# sumobot2.net
KiCad netlist of a schematic drawn in EAGLE
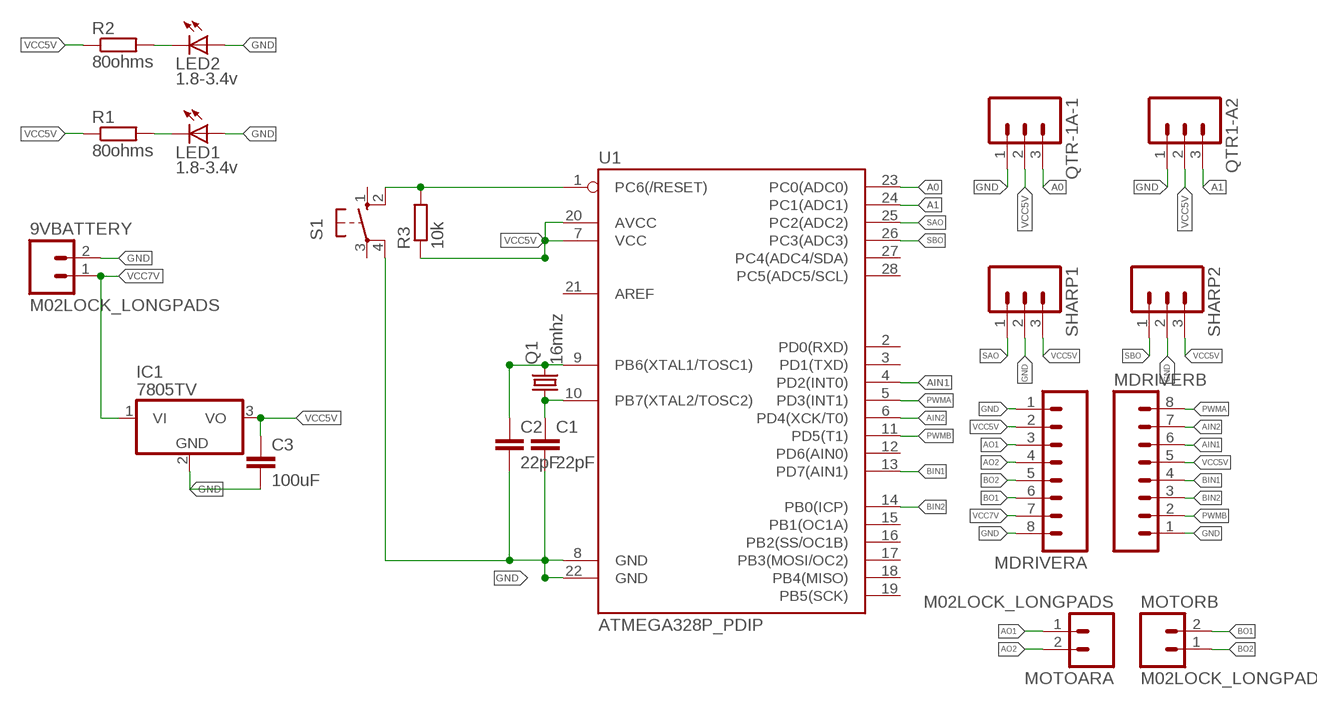
[diagram p0: schematic, sheet 1]

(export (version "E")
  (design (tool "Eeschema 10.0.6"))
  (components
    (comp (ref "9VBATTERY")
      (value "M02LOCK_LONGPADS")
      (footprint "eagle-import:1X02_LOCK_LONGPADS")
      (libsource (lib "eagle-import") (part "M02LOCK_LONGPADS"))
    )
    (comp (ref "C1")
      (value "22pF")
      (footprint "eagle-import:C025-025X050")
      (libsource (lib "eagle-import") (part "C-EU025-025X050"))
    )
    (comp (ref "C2")
      (value "22pF")
      (footprint "eagle-import:C025-025X050")
      (libsource (lib "eagle-import") (part "C-EU025-025X050"))
    )
    (comp (ref "C3")
      (value "100uF")
      (footprint "eagle-import:C025-025X050")
      (libsource (lib "eagle-import") (part "C-EU025-025X050"))
    )
    (comp (ref "IC1")
      (value "7805TV")
      (footprint "eagle-import:TO220V")
      (libsource (lib "eagle-import") (part "78TV05"))
    )
    (comp (ref "LED1")
      (value "1.8-3.4v")
      (footprint "eagle-import:LED3MM")
      (libsource (lib "eagle-import") (part "LED3MM"))
    )
    (comp (ref "LED2")
      (value "1.8-3.4v")
      (footprint "eagle-import:LED3MM")
      (libsource (lib "eagle-import") (part "LED3MM"))
    )
    (comp (ref "MDRIVERA")
      (value "M08LONGPADS")
      (footprint "eagle-import:1X08_LONGPADS")
      (libsource (lib "eagle-import") (part "M08LONGPADS"))
    )
    (comp (ref "MDRIVERB")
      (value "M08LONGPADS")
      (footprint "eagle-import:1X08_LONGPADS")
      (libsource (lib "eagle-import") (part "M08LONGPADS"))
    )
    (comp (ref "MOTOARA")
      (value "M02LOCK_LONGPADS")
      (footprint "eagle-import:1X02_LOCK_LONGPADS")
      (libsource (lib "eagle-import") (part "M02LOCK_LONGPADS"))
    )
    (comp (ref "MOTORB")
      (value "M02LOCK_LONGPADS")
      (footprint "eagle-import:1X02_LOCK_LONGPADS")
      (libsource (lib "eagle-import") (part "M02LOCK_LONGPADS"))
    )
    (comp (ref "Q1")
      (value "16mhz")
      (footprint "eagle-import:HC49U70")
      (libsource (lib "eagle-import") (part "CRYSTALHC49U70"))
    )
    (comp (ref "QTR-1A-1")
      (value "M03LONGPADS")
      (footprint "eagle-import:1X03_LONGPADS")
      (libsource (lib "eagle-import") (part "M03LONGPADS"))
    )
    (comp (ref "QTR1-A2")
      (value "M03LONGPADS")
      (footprint "eagle-import:1X03_LONGPADS")
      (libsource (lib "eagle-import") (part "M03LONGPADS"))
    )
    (comp (ref "R1")
      (value "80ohms")
      (footprint "eagle-import:0207_10")
      (libsource (lib "eagle-import") (part "R-EU_0207/10"))
    )
    (comp (ref "R2")
      (value "80ohms")
      (footprint "eagle-import:0207_10")
      (libsource (lib "eagle-import") (part "R-EU_0207/10"))
    )
    (comp (ref "R3")
      (value "10k")
      (footprint "eagle-import:0207_10")
      (libsource (lib "eagle-import") (part "R-EU_0207/10"))
    )
    (comp (ref "S1")
      (value "10-XX")
      (footprint "eagle-import:B3F-10XX")
      (fields (field (name "MPN") "B3F-1000"))
      (libsource (lib "eagle-import") (part "10-XX"))
    )
    (comp (ref "SHARP1")
      (value "M03LONGPADS")
      (footprint "eagle-import:1X03_LONGPADS")
      (libsource (lib "eagle-import") (part "M03LONGPADS"))
    )
    (comp (ref "SHARP2")
      (value "M03LONGPADS")
      (footprint "eagle-import:1X03_LONGPADS")
      (libsource (lib "eagle-import") (part "M03LONGPADS"))
    )
    (comp (ref "U1")
      (value "ATMEGA328P_PDIP")
      (footprint "eagle-import:DIL28-3")
      (libsource (lib "eagle-import") (part "ATMEGA328P_PDIP"))
    )
  )
  (nets
    (net (code "1") (name "A0") (class "Default")
      (node (ref "QTR-1A-1") (pin "3") (pinfunction "3_3") (pintype "passive"))
      (node (ref "U1") (pin "23") (pinfunction "PC0(ADC0)_23") (pintype "bidirectional"))
    )
    (net (code "2") (name "A1") (class "Default")
      (node (ref "QTR1-A2") (pin "3") (pinfunction "3_3") (pintype "passive"))
      (node (ref "U1") (pin "24") (pinfunction "PC1(ADC1)_24") (pintype "bidirectional"))
    )
    (net (code "3") (name "AIN1") (class "Default")
      (node (ref "MDRIVERB") (pin "6") (pinfunction "6_6") (pintype "passive"))
      (node (ref "U1") (pin "4") (pinfunction "PD2(INT0)_4") (pintype "bidirectional"))
    )
    (net (code "4") (name "AIN2") (class "Default")
      (node (ref "MDRIVERB") (pin "7") (pinfunction "7_7") (pintype "passive"))
      (node (ref "U1") (pin "6") (pinfunction "PD4(XCK/T0)_6") (pintype "bidirectional"))
    )
    (net (code "5") (name "AO1") (class "Default")
      (node (ref "MDRIVERA") (pin "3") (pinfunction "3_3") (pintype "passive"))
      (node (ref "MOTOARA") (pin "1") (pinfunction "1_1") (pintype "passive"))
    )
    (net (code "6") (name "AO2") (class "Default")
      (node (ref "MDRIVERA") (pin "4") (pinfunction "4_4") (pintype "passive"))
      (node (ref "MOTOARA") (pin "2") (pinfunction "2_2") (pintype "passive"))
    )
    (net (code "7") (name "BIN1") (class "Default")
      (node (ref "MDRIVERB") (pin "4") (pinfunction "4_4") (pintype "passive"))
      (node (ref "U1") (pin "13") (pinfunction "PD7(AIN1)_13") (pintype "bidirectional"))
    )
    (net (code "8") (name "BIN2") (class "Default")
      (node (ref "MDRIVERB") (pin "3") (pinfunction "3_3") (pintype "passive"))
      (node (ref "U1") (pin "14") (pinfunction "PB0(ICP)_14") (pintype "bidirectional"))
    )
    (net (code "9") (name "BO1") (class "Default")
      (node (ref "MDRIVERA") (pin "6") (pinfunction "6_6") (pintype "passive"))
      (node (ref "MOTORB") (pin "2") (pinfunction "2_2") (pintype "passive"))
    )
    (net (code "10") (name "BO2") (class "Default")
      (node (ref "MDRIVERA") (pin "5") (pinfunction "5_5") (pintype "passive"))
      (node (ref "MOTORB") (pin "1") (pinfunction "1_1") (pintype "passive"))
    )
    (net (code "11") (name "GND") (class "Default")
      (node (ref "9VBATTERY") (pin "2") (pinfunction "2_2") (pintype "passive"))
      (node (ref "C1") (pin "2") (pinfunction "2_2") (pintype "passive"))
      (node (ref "C2") (pin "2") (pinfunction "2_2") (pintype "passive"))
      (node (ref "C3") (pin "2") (pinfunction "2_2") (pintype "passive"))
      (node (ref "IC1") (pin "2") (pinfunction "GND_2") (pintype "passive"))
      (node (ref "LED1") (pin "A") (pinfunction "A_A") (pintype "passive"))
      (node (ref "LED2") (pin "A") (pinfunction "A_A") (pintype "passive"))
      (node (ref "MDRIVERA") (pin "1") (pinfunction "1_1") (pintype "passive"))
      (node (ref "MDRIVERA") (pin "8") (pinfunction "8_8") (pintype "passive"))
      (node (ref "MDRIVERB") (pin "1") (pinfunction "1_1") (pintype "passive"))
      (node (ref "QTR-1A-1") (pin "1") (pinfunction "1_1") (pintype "passive"))
      (node (ref "QTR1-A2") (pin "1") (pinfunction "1_1") (pintype "passive"))
      (node (ref "S1") (pin "4") (pinfunction "P1_4") (pintype "passive"))
      (node (ref "SHARP1") (pin "2") (pinfunction "2_2") (pintype "passive"))
      (node (ref "SHARP2") (pin "2") (pinfunction "2_2") (pintype "passive"))
      (node (ref "U1") (pin "22") (pinfunction "GND_22") (pintype "bidirectional"))
      (node (ref "U1") (pin "8") (pinfunction "GND_8") (pintype "bidirectional"))
    )
    (net (code "12") (name "Net-(LED1-C)") (class "Default")
      (node (ref "LED1") (pin "K") (pinfunction "C_K") (pintype "passive"))
      (node (ref "R1") (pin "2") (pinfunction "2_2") (pintype "passive"))
    )
    (net (code "13") (name "Net-(LED2-C)") (class "Default")
      (node (ref "LED2") (pin "K") (pinfunction "C_K") (pintype "passive"))
      (node (ref "R2") (pin "2") (pinfunction "2_2") (pintype "passive"))
    )
    (net (code "14") (name "Net-(S1-S1)") (class "Default")
      (node (ref "R3") (pin "2") (pinfunction "2_2") (pintype "passive"))
      (node (ref "S1") (pin "2") (pinfunction "S1_2") (pintype "passive"))
      (node (ref "U1") (pin "1") (pinfunction "PC6(/RESET)_1") (pintype "bidirectional"))
    )
    (net (code "15") (name "Net-(U1-PB6(XTAL1{slash}TOSC1))") (class "Default")
      (node (ref "C2") (pin "1") (pinfunction "1_1") (pintype "passive"))
      (node (ref "Q1") (pin "2") (pinfunction "2_2") (pintype "passive"))
      (node (ref "U1") (pin "9") (pinfunction "PB6(XTAL1/TOSC1)_9") (pintype "bidirectional"))
    )
    (net (code "16") (name "Net-(U1-PB7(XTAL2{slash}TOSC2))") (class "Default")
      (node (ref "C1") (pin "1") (pinfunction "1_1") (pintype "passive"))
      (node (ref "Q1") (pin "1") (pinfunction "1_1") (pintype "passive"))
      (node (ref "U1") (pin "10") (pinfunction "PB7(XTAL2/TOSC2)_10") (pintype "bidirectional"))
    )
    (net (code "17") (name "PWMA") (class "Default")
      (node (ref "MDRIVERB") (pin "8") (pinfunction "8_8") (pintype "passive"))
      (node (ref "U1") (pin "5") (pinfunction "PD3(INT1)_5") (pintype "bidirectional"))
    )
    (net (code "18") (name "PWMB") (class "Default")
      (node (ref "MDRIVERB") (pin "2") (pinfunction "2_2") (pintype "passive"))
      (node (ref "U1") (pin "11") (pinfunction "PD5(T1)_11") (pintype "bidirectional"))
    )
    (net (code "19") (name "SAO") (class "Default")
      (node (ref "SHARP1") (pin "1") (pinfunction "1_1") (pintype "passive"))
      (node (ref "U1") (pin "25") (pinfunction "PC2(ADC2)_25") (pintype "bidirectional"))
    )
    (net (code "20") (name "SBO") (class "Default")
      (node (ref "SHARP2") (pin "1") (pinfunction "1_1") (pintype "passive"))
      (node (ref "U1") (pin "26") (pinfunction "PC3(ADC3)_26") (pintype "bidirectional"))
    )
    (net (code "21") (name "VCC5V") (class "Default")
      (node (ref "C3") (pin "1") (pinfunction "1_1") (pintype "passive"))
      (node (ref "IC1") (pin "3") (pinfunction "VO_3") (pintype "passive"))
      (node (ref "MDRIVERA") (pin "2") (pinfunction "2_2") (pintype "passive"))
      (node (ref "MDRIVERB") (pin "5") (pinfunction "5_5") (pintype "passive"))
      (node (ref "QTR-1A-1") (pin "2") (pinfunction "2_2") (pintype "passive"))
      (node (ref "QTR1-A2") (pin "2") (pinfunction "2_2") (pintype "passive"))
      (node (ref "R1") (pin "1") (pinfunction "1_1") (pintype "passive"))
      (node (ref "R2") (pin "1") (pinfunction "1_1") (pintype "passive"))
      (node (ref "R3") (pin "1") (pinfunction "1_1") (pintype "passive"))
      (node (ref "SHARP1") (pin "3") (pinfunction "3_3") (pintype "passive"))
      (node (ref "SHARP2") (pin "3") (pinfunction "3_3") (pintype "passive"))
      (node (ref "U1") (pin "20") (pinfunction "AVCC_20") (pintype "bidirectional"))
      (node (ref "U1") (pin "7") (pinfunction "VCC_7") (pintype "bidirectional"))
    )
    (net (code "22") (name "VCC7V") (class "Default")
      (node (ref "9VBATTERY") (pin "1") (pinfunction "1_1") (pintype "passive"))
      (node (ref "IC1") (pin "1") (pinfunction "VI_1") (pintype "input"))
      (node (ref "MDRIVERA") (pin "7") (pinfunction "7_7") (pintype "passive"))
    )
    (net (code "23") (name "unconnected-(S1-P-Pad3)") (class "Default")
      (node (ref "S1") (pin "3") (pinfunction "P_3") (pintype "passive"))
    )
    (net (code "24") (name "unconnected-(S1-S-Pad1)") (class "Default")
      (node (ref "S1") (pin "1") (pinfunction "S_1") (pintype "passive"))
    )
    (net (code "25") (name "unconnected-(U1-AREF-Pad21)") (class "Default")
      (node (ref "U1") (pin "21") (pinfunction "AREF_21") (pintype "bidirectional"))
    )
    (net (code "26") (name "unconnected-(U1-PB1(OC1A)-Pad15)") (class "Default")
      (node (ref "U1") (pin "15") (pinfunction "PB1(OC1A)_15") (pintype "bidirectional"))
    )
    (net (code "27") (name "unconnected-(U1-PB2(SS{slash}OC1B)-Pad16)") (class "Default")
      (node (ref "U1") (pin "16") (pinfunction "PB2(SS/OC1B)_16") (pintype "bidirectional"))
    )
    (net (code "28") (name "unconnected-(U1-PB3(MOSI{slash}OC2)-Pad17)") (class "Default")
      (node (ref "U1") (pin "17") (pinfunction "PB3(MOSI/OC2)_17") (pintype "bidirectional"))
    )
    (net (code "29") (name "unconnected-(U1-PB4(MISO)-Pad18)") (class "Default")
      (node (ref "U1") (pin "18") (pinfunction "PB4(MISO)_18") (pintype "bidirectional"))
    )
    (net (code "30") (name "unconnected-(U1-PB5(SCK)-Pad19)") (class "Default")
      (node (ref "U1") (pin "19") (pinfunction "PB5(SCK)_19") (pintype "bidirectional"))
    )
    (net (code "31") (name "unconnected-(U1-PC4(ADC4{slash}SDA)-Pad27)") (class "Default")
      (node (ref "U1") (pin "27") (pinfunction "PC4(ADC4/SDA)_27") (pintype "bidirectional"))
    )
    (net (code "32") (name "unconnected-(U1-PC5(ADC5{slash}SCL)-Pad28)") (class "Default")
      (node (ref "U1") (pin "28") (pinfunction "PC5(ADC5/SCL)_28") (pintype "bidirectional"))
    )
    (net (code "33") (name "unconnected-(U1-PD0(RXD)-Pad2)") (class "Default")
      (node (ref "U1") (pin "2") (pinfunction "PD0(RXD)_2") (pintype "bidirectional"))
    )
    (net (code "34") (name "unconnected-(U1-PD1(TXD)-Pad3)") (class "Default")
      (node (ref "U1") (pin "3") (pinfunction "PD1(TXD)_3") (pintype "bidirectional"))
    )
    (net (code "35") (name "unconnected-(U1-PD6(AIN0)-Pad12)") (class "Default")
      (node (ref "U1") (pin "12") (pinfunction "PD6(AIN0)_12") (pintype "bidirectional"))
    )
  )
)
